# microSD_Display.net
KiCad netlist of a schematic drawn in Altium Designer
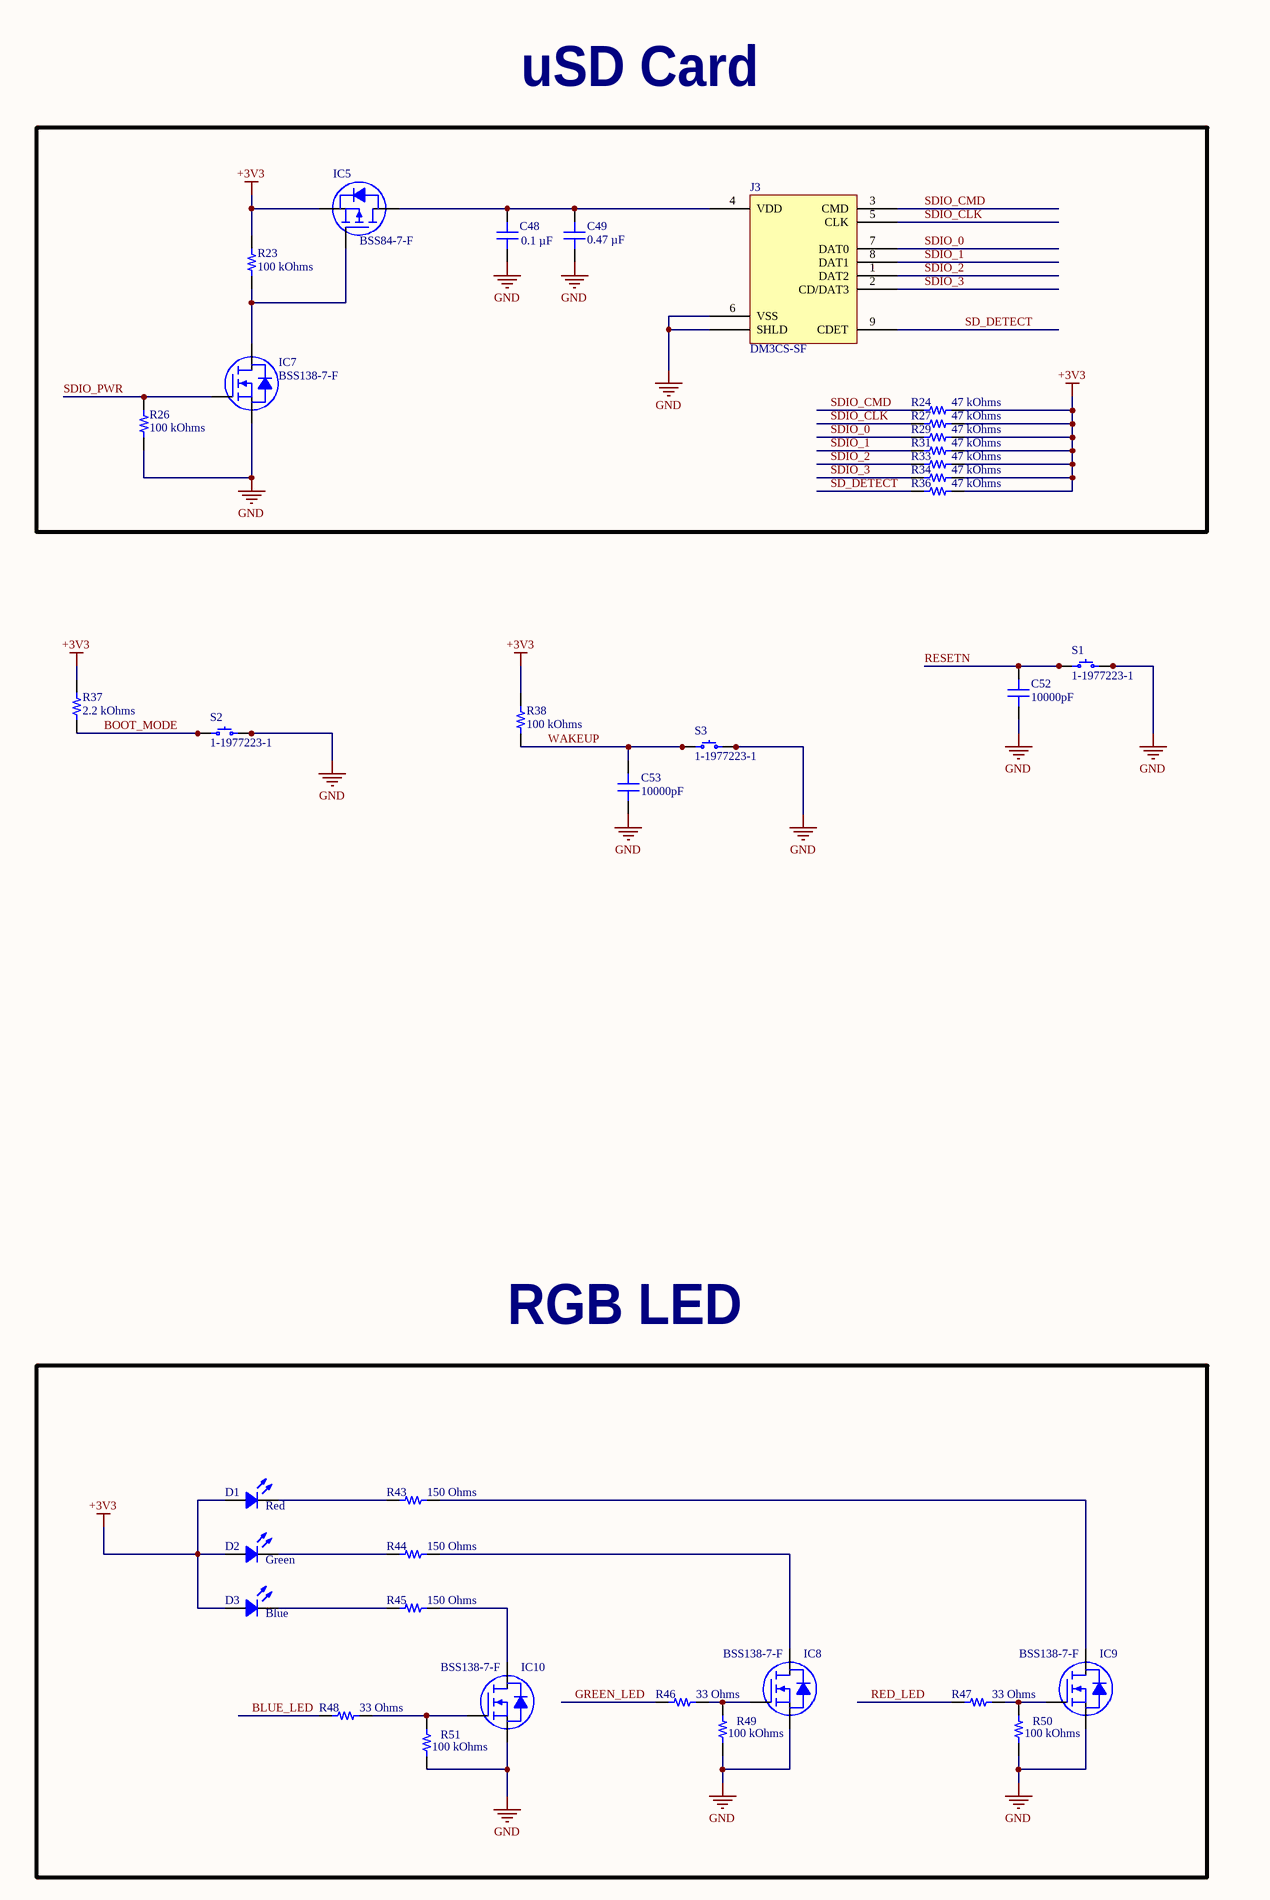
[diagram p0: microSD_Display.SchDoc, left]
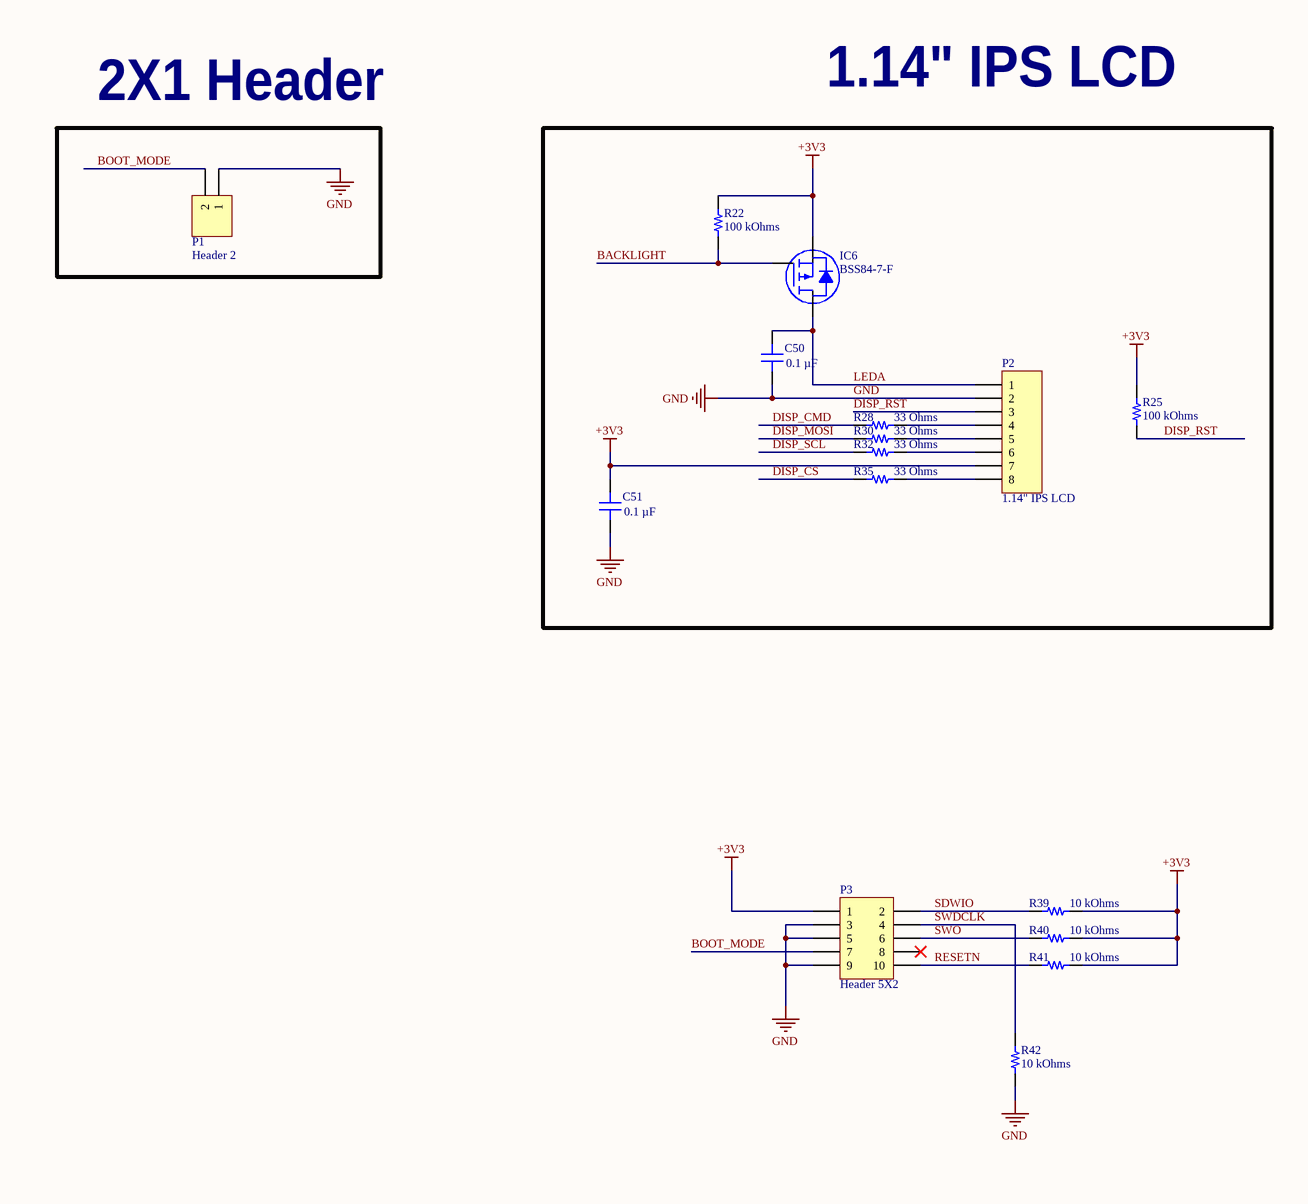
[diagram p1: microSD_Display.SchDoc, right]

(export (version "E")
  (design (tool "Eeschema 10.0.6"))
  (components
    (comp (ref "C48")
      (value "0.1 µF")
      (footprint "CAP 0603_1608")
      (description "CAP CER 0.1UF 16V X7R 0603")
      (fields (field (name "PART NUMBER") "CS0603KRX7R7BB104") (field (name "MANUFACTURER") "Yageo"))
      (libsource (lib "Celestial Altium Library - altium_library") (part "Capacitor"))
    )
    (comp (ref "C49")
      (value "0.47 µF")
      (footprint "CAP 0603_1608")
      (description "CAP CER 0.47UF 16V X5R 0603")
      (fields
        (field (name "PART NUMBER") "0603X474K160CT")
        (field (name "MANUFACTURER") "Walsin Technology Corporation")
      )
      (libsource (lib "Celestial Altium Library - altium_library") (part "Capacitor"))
    )
    (comp (ref "C50")
      (value "0.1 µF")
      (footprint "CAP 0603_1608")
      (description "CAP CER 0.1UF 16V X7R 0603")
      (fields (field (name "PART NUMBER") "CS0603KRX7R7BB104") (field (name "MANUFACTURER") "Yageo"))
      (libsource (lib "Celestial Altium Library - altium_library") (part "Capacitor"))
    )
    (comp (ref "C51")
      (value "0.1 µF")
      (footprint "CAP 0603_1608")
      (description "CAP CER 0.1UF 16V X7R 0603")
      (fields (field (name "PART NUMBER") "CS0603KRX7R7BB104") (field (name "MANUFACTURER") "Yageo"))
      (libsource (lib "Celestial Altium Library - altium_library") (part "Capacitor"))
    )
    (comp (ref "C52")
      (value "10000pF")
      (footprint "CAP 0603_1608")
      (description "CAP CER 10000PF 16V X7R 0603")
      (fields (field (name "PART NUMBER") "0603YC103KAT2A") (field (name "MANUFACTURER") "AVX Corporation"))
      (libsource (lib "Celestial Altium Library - altium_library") (part "Capacitor"))
    )
    (comp (ref "C53")
      (value "10000pF")
      (footprint "CAP 0603_1608")
      (description "CAP CER 10000PF 16V X7R 0603")
      (fields (field (name "PART NUMBER") "0603YC103KAT2A") (field (name "MANUFACTURER") "AVX Corporation"))
      (libsource (lib "Celestial Altium Library - altium_library") (part "Capacitor"))
    )
    (comp (ref "D1")
      (value "Red")
      (footprint "LED 0603_1608 RED")
      (description "LED RED DIFFUSED SURFACE MOUNT")
      (fields (field (name "PART NUMBER") "FKR1111C-TR") (field (name "MANUFACTURER") "Stanley Electric Co"))
      (libsource (lib "Celestial Altium Library - altium_library") (part "LED"))
    )
    (comp (ref "D2")
      (value "Green")
      (footprint "LED 0603_1608 GREEN")
      (description "LED GREEN DIFFUSED 0603 SMD")
      (fields (field (name "PART NUMBER") "HSME-C130") (field (name "MANUFACTURER") "Broadcom Limited"))
      (libsource (lib "Celestial Altium Library - altium_library") (part "LED"))
    )
    (comp (ref "D3")
      (value "Blue")
      (footprint "LED 0603_1608 BLUE")
      (description "LED BLUE 0603 SMD")
      (fields (field (name "PART NUMBER") "5973604507F") (field (name "MANUFACTURER") "Dialight"))
      (libsource (lib "Celestial Altium Library - altium_library") (part "LED"))
    )
    (comp (ref "IC5")
      (value "BSS84-7-F")
      (footprint "DIODES SOT-23-3")
      (description "MOSFET P-CH 50V 130MA SOT23-3")
      (fields (field (name "MANUFACTURER") "Diodes Incorporated"))
      (libsource (lib "Celestial Altium Library - altium_library") (part "DIODES MOSFET P-CH SOT-23-3"))
    )
    (comp (ref "IC6")
      (value "BSS84-7-F")
      (footprint "DIODES SOT-23-3")
      (description "MOSFET P-CH 50V 130MA SOT23-3")
      (fields (field (name "MANUFACTURER") "Diodes Incorporated"))
      (libsource (lib "Celestial Altium Library - altium_library") (part "DIODES MOSFET P-CH SOT-23-3"))
    )
    (comp (ref "IC7")
      (value "BSS138-7-F")
      (footprint "DIODES SOT-23-3")
      (description "MOSFET N-CH 50V 200MA SOT23-3")
      (fields (field (name "MANUFACTURER") "Diodes Incorporated"))
      (libsource (lib "Celestial Altium Library - altium_library") (part "DIODES INC MOSFET N-CH SOT-23-3"))
    )
    (comp (ref "IC8")
      (value "BSS138-7-F")
      (footprint "DIODES SOT-23-3")
      (description "MOSFET N-CH 50V 200MA SOT23-3")
      (fields (field (name "MANUFACTURER") "Diodes Incorporated"))
      (libsource (lib "Celestial Altium Library - altium_library") (part "DIODES INC MOSFET N-CH SOT-23-3"))
    )
    (comp (ref "IC9")
      (value "BSS138-7-F")
      (footprint "DIODES SOT-23-3")
      (description "MOSFET N-CH 50V 200MA SOT23-3")
      (fields (field (name "MANUFACTURER") "Diodes Incorporated"))
      (libsource (lib "Celestial Altium Library - altium_library") (part "DIODES INC MOSFET N-CH SOT-23-3"))
    )
    (comp (ref "IC10")
      (value "BSS138-7-F")
      (footprint "DIODES SOT-23-3")
      (description "MOSFET N-CH 50V 200MA SOT23-3")
      (fields (field (name "MANUFACTURER") "Diodes Incorporated"))
      (libsource (lib "Celestial Altium Library - altium_library") (part "DIODES INC MOSFET N-CH SOT-23-3"))
    )
    (comp (ref "J3")
      (value "DM3CS-SF")
      (footprint "HIROSE DM3CS")
      (description "CONN MICRO SD CARD HINGED TYPE")
      (fields (field (name "MANUFACTURER") "Hirose Electric Co Ltd"))
      (libsource (lib "Celestial Altium Library - altium_library") (part "Hirose DM3C MicroSD"))
    )
    (comp (ref "P1")
      (value "Header 2")
      (footprint "HDR1X2")
      (description "Header, 2-Pin")
      (fields (field (name "PUBLISHER") "Altium Limited"))
      (libsource (lib "Miscellaneous Connectors") (part "Header 2"))
    )
    (comp (ref "P2")
      (value "1.14\" IPS LCD")
      (footprint "HDR1X8")
      (description "Header, 8-Pin")
      (fields (field (name "PUBLISHER") "Altium Limited"))
      (libsource (lib "Miscellaneous Connectors") (part "Header 8"))
    )
    (comp (ref "P3")
      (value "Header 5X2")
      (footprint "HDR2X5")
      (description "Header, 5-Pin, Dual row")
      (fields (field (name "PUBLISHER") "Altium Limited"))
      (libsource (lib "Miscellaneous Connectors") (part "Header 5X2"))
    )
    (comp (ref "R22")
      (value "100 kOhms")
      (footprint "RES 0603_1608")
      (description "RES 100 KOHMS 0.5% 1/10W 0603")
      (fields
        (field (name "PART NUMBER") "ERA-3AED104V")
        (field (name "MANUFACTURER") "Panasonic Electronic Components")
      )
      (libsource (lib "Celestial Altium Library - altium_library") (part "Resistor"))
    )
    (comp (ref "R23")
      (value "100 kOhms")
      (footprint "RES 0603_1608")
      (description "RES 100 KOHMS 0.5% 1/10W 0603")
      (fields
        (field (name "PART NUMBER") "ERA-3AED104V")
        (field (name "MANUFACTURER") "Panasonic Electronic Components")
      )
      (libsource (lib "Celestial Altium Library - altium_library") (part "Resistor"))
    )
    (comp (ref "R24")
      (value "47 kOhms")
      (footprint "RES 0603_1608")
      (description "RES 47K OHM 5% 1/4W 0603")
      (fields
        (field (name "PART NUMBER") "ERJ-UP3J473V")
        (field (name "MANUFACTURER") "Panasonic Electronic Components")
      )
      (libsource (lib "Celestial Altium Library - altium_library") (part "Resistor"))
    )
    (comp (ref "R25")
      (value "100 kOhms")
      (footprint "RES 0603_1608")
      (description "RES 100 KOHMS 0.5% 1/10W 0603")
      (fields
        (field (name "PART NUMBER") "ERA-3AED104V")
        (field (name "MANUFACTURER") "Panasonic Electronic Components")
      )
      (libsource (lib "Celestial Altium Library - altium_library") (part "Resistor"))
    )
    (comp (ref "R26")
      (value "100 kOhms")
      (footprint "RES 0603_1608")
      (description "RES 100 KOHMS 0.5% 1/10W 0603")
      (fields
        (field (name "PART NUMBER") "ERA-3AED104V")
        (field (name "MANUFACTURER") "Panasonic Electronic Components")
      )
      (libsource (lib "Celestial Altium Library - altium_library") (part "Resistor"))
    )
    (comp (ref "R27")
      (value "47 kOhms")
      (footprint "RES 0603_1608")
      (description "RES 47K OHM 5% 1/4W 0603")
      (fields
        (field (name "PART NUMBER") "ERJ-UP3J473V")
        (field (name "MANUFACTURER") "Panasonic Electronic Components")
      )
      (libsource (lib "Celestial Altium Library - altium_library") (part "Resistor"))
    )
    (comp (ref "R28")
      (value "33 Ohms")
      (footprint "RES 0603_1608")
      (description "RES SMD 33 OHM 1% 1/10W 0603")
      (fields (field (name "PART NUMBER") "AC0603FR-0733RL") (field (name "MANUFACTURER") "Yageo"))
      (libsource (lib "Celestial Altium Library - altium_library") (part "Resistor"))
    )
    (comp (ref "R29")
      (value "47 kOhms")
      (footprint "RES 0603_1608")
      (description "RES 47K OHM 5% 1/4W 0603")
      (fields
        (field (name "PART NUMBER") "ERJ-UP3J473V")
        (field (name "MANUFACTURER") "Panasonic Electronic Components")
      )
      (libsource (lib "Celestial Altium Library - altium_library") (part "Resistor"))
    )
    (comp (ref "R30")
      (value "33 Ohms")
      (footprint "RES 0603_1608")
      (description "RES SMD 33 OHM 1% 1/10W 0603")
      (fields (field (name "PART NUMBER") "AC0603FR-0733RL") (field (name "MANUFACTURER") "Yageo"))
      (libsource (lib "Celestial Altium Library - altium_library") (part "Resistor"))
    )
    (comp (ref "R31")
      (value "47 kOhms")
      (footprint "RES 0603_1608")
      (description "RES 47K OHM 5% 1/4W 0603")
      (fields
        (field (name "PART NUMBER") "ERJ-UP3J473V")
        (field (name "MANUFACTURER") "Panasonic Electronic Components")
      )
      (libsource (lib "Celestial Altium Library - altium_library") (part "Resistor"))
    )
    (comp (ref "R32")
      (value "33 Ohms")
      (footprint "RES 0603_1608")
      (description "RES SMD 33 OHM 1% 1/10W 0603")
      (fields (field (name "PART NUMBER") "AC0603FR-0733RL") (field (name "MANUFACTURER") "Yageo"))
      (libsource (lib "Celestial Altium Library - altium_library") (part "Resistor"))
    )
    (comp (ref "R33")
      (value "47 kOhms")
      (footprint "RES 0603_1608")
      (description "RES 47K OHM 5% 1/4W 0603")
      (fields
        (field (name "PART NUMBER") "ERJ-UP3J473V")
        (field (name "MANUFACTURER") "Panasonic Electronic Components")
      )
      (libsource (lib "Celestial Altium Library - altium_library") (part "Resistor"))
    )
    (comp (ref "R34")
      (value "47 kOhms")
      (footprint "RES 0603_1608")
      (description "RES 47K OHM 5% 1/4W 0603")
      (fields
        (field (name "PART NUMBER") "ERJ-UP3J473V")
        (field (name "MANUFACTURER") "Panasonic Electronic Components")
      )
      (libsource (lib "Celestial Altium Library - altium_library") (part "Resistor"))
    )
    (comp (ref "R35")
      (value "33 Ohms")
      (footprint "RES 0603_1608")
      (description "RES SMD 33 OHM 1% 1/10W 0603")
      (fields (field (name "PART NUMBER") "AC0603FR-0733RL") (field (name "MANUFACTURER") "Yageo"))
      (libsource (lib "Celestial Altium Library - altium_library") (part "Resistor"))
    )
    (comp (ref "R36")
      (value "47 kOhms")
      (footprint "RES 0603_1608")
      (description "RES 47K OHM 5% 1/4W 0603")
      (fields
        (field (name "PART NUMBER") "ERJ-UP3J473V")
        (field (name "MANUFACTURER") "Panasonic Electronic Components")
      )
      (libsource (lib "Celestial Altium Library - altium_library") (part "Resistor"))
    )
    (comp (ref "R37")
      (value "2.2 kOhms")
      (footprint "RES 0603_1608")
      (description "RES SMD 2.2K OHM 1% 1/10W 0603")
      (fields (field (name "PART NUMBER") "AC0603FR-072K2L") (field (name "MANUFACTURER") "Yageo"))
      (libsource (lib "Celestial Altium Library - altium_library") (part "Resistor"))
    )
    (comp (ref "R38")
      (value "100 kOhms")
      (footprint "RES 0603_1608")
      (description "RES 100 KOHMS 0.5% 1/10W 0603")
      (fields
        (field (name "PART NUMBER") "ERA-3AED104V")
        (field (name "MANUFACTURER") "Panasonic Electronic Components")
      )
      (libsource (lib "Celestial Altium Library - altium_library") (part "Resistor"))
    )
    (comp (ref "R39")
      (value "10 kOhms")
      (footprint "RES 0603_1608")
      (description "RES SMD 10K OHM 1% 1/10W 0603")
      (fields (field (name "PART NUMBER") "AA0603FR-0710KL") (field (name "MANUFACTURER") "Yageo"))
      (libsource (lib "Celestial Altium Library - altium_library") (part "Resistor"))
    )
    (comp (ref "R40")
      (value "10 kOhms")
      (footprint "RES 0603_1608")
      (description "RES SMD 10K OHM 1% 1/10W 0603")
      (fields (field (name "PART NUMBER") "AA0603FR-0710KL") (field (name "MANUFACTURER") "Yageo"))
      (libsource (lib "Celestial Altium Library - altium_library") (part "Resistor"))
    )
    (comp (ref "R41")
      (value "10 kOhms")
      (footprint "RES 0603_1608")
      (description "RES SMD 10K OHM 1% 1/10W 0603")
      (fields (field (name "PART NUMBER") "AA0603FR-0710KL") (field (name "MANUFACTURER") "Yageo"))
      (libsource (lib "Celestial Altium Library - altium_library") (part "Resistor"))
    )
    (comp (ref "R42")
      (value "10 kOhms")
      (footprint "RES 0603_1608")
      (description "RES SMD 10K OHM 1% 1/10W 0603")
      (fields (field (name "PART NUMBER") "AA0603FR-0710KL") (field (name "MANUFACTURER") "Yageo"))
      (libsource (lib "Celestial Altium Library - altium_library") (part "Resistor"))
    )
    (comp (ref "R43")
      (value "150 Ohms")
      (footprint "RES 0603_1608")
      (description "RES SMD 150 OHM 5% 1/10W 0603")
      (fields (field (name "PART NUMBER") "CR0603-JW-151ELF") (field (name "MANUFACTURER") "Bourns Inc."))
      (libsource (lib "Celestial Altium Library - altium_library") (part "Resistor"))
    )
    (comp (ref "R44")
      (value "150 Ohms")
      (footprint "RES 0603_1608")
      (description "RES SMD 150 OHM 5% 1/10W 0603")
      (fields (field (name "PART NUMBER") "CR0603-JW-151ELF") (field (name "MANUFACTURER") "Bourns Inc."))
      (libsource (lib "Celestial Altium Library - altium_library") (part "Resistor"))
    )
    (comp (ref "R45")
      (value "150 Ohms")
      (footprint "RES 0603_1608")
      (description "RES SMD 150 OHM 5% 1/10W 0603")
      (fields (field (name "PART NUMBER") "CR0603-JW-151ELF") (field (name "MANUFACTURER") "Bourns Inc."))
      (libsource (lib "Celestial Altium Library - altium_library") (part "Resistor"))
    )
    (comp (ref "R46")
      (value "33 Ohms")
      (footprint "RES 0603_1608")
      (description "RES SMD 33 OHM 1% 1/10W 0603")
      (fields (field (name "PART NUMBER") "AC0603FR-0733RL") (field (name "MANUFACTURER") "Yageo"))
      (libsource (lib "Celestial Altium Library - altium_library") (part "Resistor"))
    )
    (comp (ref "R47")
      (value "33 Ohms")
      (footprint "RES 0603_1608")
      (description "RES SMD 33 OHM 1% 1/10W 0603")
      (fields (field (name "PART NUMBER") "AC0603FR-0733RL") (field (name "MANUFACTURER") "Yageo"))
      (libsource (lib "Celestial Altium Library - altium_library") (part "Resistor"))
    )
    (comp (ref "R48")
      (value "33 Ohms")
      (footprint "RES 0603_1608")
      (description "RES SMD 33 OHM 1% 1/10W 0603")
      (fields (field (name "PART NUMBER") "AC0603FR-0733RL") (field (name "MANUFACTURER") "Yageo"))
      (libsource (lib "Celestial Altium Library - altium_library") (part "Resistor"))
    )
    (comp (ref "R49")
      (value "100 kOhms")
      (footprint "RES 0603_1608")
      (description "RES 100 KOHMS 0.5% 1/10W 0603")
      (fields
        (field (name "PART NUMBER") "ERA-3AED104V")
        (field (name "MANUFACTURER") "Panasonic Electronic Components")
      )
      (libsource (lib "Celestial Altium Library - altium_library") (part "Resistor"))
    )
    (comp (ref "R50")
      (value "100 kOhms")
      (footprint "RES 0603_1608")
      (description "RES 100 KOHMS 0.5% 1/10W 0603")
      (fields
        (field (name "PART NUMBER") "ERA-3AED104V")
        (field (name "MANUFACTURER") "Panasonic Electronic Components")
      )
      (libsource (lib "Celestial Altium Library - altium_library") (part "Resistor"))
    )
    (comp (ref "R51")
      (value "100 kOhms")
      (footprint "RES 0603_1608")
      (description "RES 100 KOHMS 0.5% 1/10W 0603")
      (fields
        (field (name "PART NUMBER") "ERA-3AED104V")
        (field (name "MANUFACTURER") "Panasonic Electronic Components")
      )
      (libsource (lib "Celestial Altium Library - altium_library") (part "Resistor"))
    )
    (comp (ref "S1")
      (value "1-1977223-1")
      (footprint "TE FSM4JSMA")
      (description "SWITCH TACTILE SPST-NO 0.05A 24V")
      (fields (field (name "MANUFACTURER") "TE Connectivity ALCOSWITCH Switches"))
      (libsource (lib "Celestial Altium Library - altium_library") (part "SPST-NO 4 PIN"))
    )
    (comp (ref "S2")
      (value "1-1977223-1")
      (footprint "TE FSM4JSMA")
      (description "SWITCH TACTILE SPST-NO 0.05A 24V")
      (fields (field (name "MANUFACTURER") "TE Connectivity ALCOSWITCH Switches"))
      (libsource (lib "Celestial Altium Library - altium_library") (part "SPST-NO 4 PIN"))
    )
    (comp (ref "S3")
      (value "1-1977223-1")
      (footprint "TE FSM4JSMA")
      (description "SWITCH TACTILE SPST-NO 0.05A 24V")
      (fields (field (name "MANUFACTURER") "TE Connectivity ALCOSWITCH Switches"))
      (libsource (lib "Celestial Altium Library - altium_library") (part "SPST-NO 4 PIN"))
    )
  )
  (nets
    (net (code "1") (name "+3V3") (class "Default")
      (node (ref "C51") (pin "2") (pinfunction "2_2") (pintype "passive"))
      (node (ref "D1") (pin "1") (pinfunction "1_1") (pintype "passive"))
      (node (ref "D2") (pin "1") (pinfunction "1_1") (pintype "passive"))
      (node (ref "D3") (pin "1") (pinfunction "1_1") (pintype "passive"))
      (node (ref "IC5") (pin "2") (pinfunction "S_2") (pintype "passive"))
      (node (ref "IC6") (pin "2") (pinfunction "S_2") (pintype "passive"))
      (node (ref "P2") (pin "7") (pinfunction "7_7") (pintype "passive"))
      (node (ref "P3") (pin "1") (pinfunction "1_1") (pintype "passive"))
      (node (ref "R22") (pin "2") (pinfunction "2_2") (pintype "passive"))
      (node (ref "R23") (pin "2") (pinfunction "2_2") (pintype "passive"))
      (node (ref "R24") (pin "2") (pinfunction "2_2") (pintype "passive"))
      (node (ref "R25") (pin "2") (pinfunction "2_2") (pintype "passive"))
      (node (ref "R27") (pin "2") (pinfunction "2_2") (pintype "passive"))
      (node (ref "R29") (pin "2") (pinfunction "2_2") (pintype "passive"))
      (node (ref "R31") (pin "2") (pinfunction "2_2") (pintype "passive"))
      (node (ref "R33") (pin "2") (pinfunction "2_2") (pintype "passive"))
      (node (ref "R34") (pin "2") (pinfunction "2_2") (pintype "passive"))
      (node (ref "R36") (pin "2") (pinfunction "2_2") (pintype "passive"))
      (node (ref "R37") (pin "2") (pinfunction "2_2") (pintype "passive"))
      (node (ref "R38") (pin "2") (pinfunction "2_2") (pintype "passive"))
      (node (ref "R39") (pin "2") (pinfunction "2_2") (pintype "passive"))
      (node (ref "R40") (pin "2") (pinfunction "2_2") (pintype "passive"))
      (node (ref "R41") (pin "2") (pinfunction "2_2") (pintype "passive"))
    )
    (net (code "2") (name "/BACKLIGHT") (class "Default")
      (node (ref "IC6") (pin "1") (pinfunction "G_1") (pintype "passive"))
      (node (ref "R22") (pin "1") (pinfunction "1_1") (pintype "passive"))
    )
    (net (code "3") (name "/BLUE_LED") (class "Default")
      (node (ref "R48") (pin "1") (pinfunction "1_1") (pintype "passive"))
    )
    (net (code "4") (name "/BOOT_MODE") (class "Default")
      (node (ref "P1") (pin "2") (pinfunction "2_2") (pintype "passive"))
      (node (ref "P3") (pin "7") (pinfunction "7_7") (pintype "passive"))
      (node (ref "R37") (pin "1") (pinfunction "1_1") (pintype "passive"))
      (node (ref "S2") (pin "1") (pinfunction "1_1") (pintype "passive"))
      (node (ref "S2") (pin "2") (pinfunction "2_2") (pintype "passive"))
    )
    (net (code "5") (name "/DISP_CMD") (class "Default")
      (node (ref "R28") (pin "1") (pinfunction "1_1") (pintype "passive"))
    )
    (net (code "6") (name "/DISP_CS") (class "Default")
      (node (ref "R35") (pin "1") (pinfunction "1_1") (pintype "passive"))
    )
    (net (code "7") (name "/DISP_MOSI") (class "Default")
      (node (ref "R30") (pin "1") (pinfunction "1_1") (pintype "passive"))
    )
    (net (code "8") (name "/DISP_RST") (class "Default")
      (node (ref "P2") (pin "3") (pinfunction "3_3") (pintype "passive"))
      (node (ref "R25") (pin "1") (pinfunction "1_1") (pintype "passive"))
    )
    (net (code "9") (name "/DISP_SCL") (class "Default")
      (node (ref "R32") (pin "1") (pinfunction "1_1") (pintype "passive"))
    )
    (net (code "10") (name "/GREEN_LED") (class "Default")
      (node (ref "R46") (pin "1") (pinfunction "1_1") (pintype "passive"))
    )
    (net (code "11") (name "/LEDA") (class "Default")
      (node (ref "C50") (pin "2") (pinfunction "2_2") (pintype "passive"))
      (node (ref "IC6") (pin "3") (pinfunction "D_3") (pintype "passive"))
      (node (ref "P2") (pin "1") (pinfunction "1_1") (pintype "passive"))
    )
    (net (code "12") (name "/RED_LED") (class "Default")
      (node (ref "R47") (pin "1") (pinfunction "1_1") (pintype "passive"))
    )
    (net (code "13") (name "/RESETN") (class "Default")
      (node (ref "C52") (pin "2") (pinfunction "2_2") (pintype "passive"))
      (node (ref "P3") (pin "10") (pinfunction "10_10") (pintype "passive"))
      (node (ref "R41") (pin "1") (pinfunction "1_1") (pintype "passive"))
      (node (ref "S1") (pin "1") (pinfunction "1_1") (pintype "passive"))
      (node (ref "S1") (pin "2") (pinfunction "2_2") (pintype "passive"))
    )
    (net (code "14") (name "/SDIO_0") (class "Default")
      (node (ref "J3") (pin "7") (pinfunction "DAT0_7") (pintype "passive"))
      (node (ref "R29") (pin "1") (pinfunction "1_1") (pintype "passive"))
    )
    (net (code "15") (name "/SDIO_1") (class "Default")
      (node (ref "J3") (pin "8") (pinfunction "DAT1_8") (pintype "passive"))
      (node (ref "R31") (pin "1") (pinfunction "1_1") (pintype "passive"))
    )
    (net (code "16") (name "/SDIO_2") (class "Default")
      (node (ref "J3") (pin "1") (pinfunction "DAT2_1") (pintype "passive"))
      (node (ref "R33") (pin "1") (pinfunction "1_1") (pintype "passive"))
    )
    (net (code "17") (name "/SDIO_3") (class "Default")
      (node (ref "J3") (pin "2") (pinfunction "CD/DAT3_2") (pintype "passive"))
      (node (ref "R34") (pin "1") (pinfunction "1_1") (pintype "passive"))
    )
    (net (code "18") (name "/SDIO_CLK") (class "Default")
      (node (ref "J3") (pin "5") (pinfunction "CLK_5") (pintype "passive"))
      (node (ref "R27") (pin "1") (pinfunction "1_1") (pintype "passive"))
    )
    (net (code "19") (name "/SDIO_CMD") (class "Default")
      (node (ref "J3") (pin "3") (pinfunction "CMD_3") (pintype "passive"))
      (node (ref "R24") (pin "1") (pinfunction "1_1") (pintype "passive"))
    )
    (net (code "20") (name "/SDIO_PWR") (class "Default")
      (node (ref "IC7") (pin "1") (pinfunction "G_1") (pintype "passive"))
      (node (ref "R26") (pin "2") (pinfunction "2_2") (pintype "passive"))
    )
    (net (code "21") (name "/SDWIO") (class "Default")
      (node (ref "P3") (pin "2") (pinfunction "2_2") (pintype "passive"))
      (node (ref "R39") (pin "1") (pinfunction "1_1") (pintype "passive"))
    )
    (net (code "22") (name "/SD_DETECT") (class "Default")
      (node (ref "J3") (pin "9") (pinfunction "CDET_9") (pintype "passive"))
      (node (ref "R36") (pin "1") (pinfunction "1_1") (pintype "passive"))
    )
    (net (code "23") (name "/SWDCLK") (class "Default")
      (node (ref "P3") (pin "4") (pinfunction "4_4") (pintype "passive"))
      (node (ref "R42") (pin "2") (pinfunction "2_2") (pintype "passive"))
    )
    (net (code "24") (name "/SWO") (class "Default")
      (node (ref "P3") (pin "6") (pinfunction "6_6") (pintype "passive"))
      (node (ref "R40") (pin "1") (pinfunction "1_1") (pintype "passive"))
    )
    (net (code "25") (name "/WAKEUP") (class "Default")
      (node (ref "C53") (pin "2") (pinfunction "2_2") (pintype "passive"))
      (node (ref "R38") (pin "1") (pinfunction "1_1") (pintype "passive"))
      (node (ref "S3") (pin "1") (pinfunction "1_1") (pintype "passive"))
      (node (ref "S3") (pin "2") (pinfunction "2_2") (pintype "passive"))
    )
    (net (code "26") (name "GND") (class "Default")
      (node (ref "C48") (pin "1") (pinfunction "1_1") (pintype "passive"))
      (node (ref "C49") (pin "1") (pinfunction "1_1") (pintype "passive"))
      (node (ref "C50") (pin "1") (pinfunction "1_1") (pintype "passive"))
      (node (ref "C51") (pin "1") (pinfunction "1_1") (pintype "passive"))
      (node (ref "C52") (pin "1") (pinfunction "1_1") (pintype "passive"))
      (node (ref "C53") (pin "1") (pinfunction "1_1") (pintype "passive"))
      (node (ref "IC10") (pin "2") (pinfunction "S_2") (pintype "passive"))
      (node (ref "IC7") (pin "2") (pinfunction "S_2") (pintype "passive"))
      (node (ref "IC8") (pin "2") (pinfunction "S_2") (pintype "passive"))
      (node (ref "IC9") (pin "2") (pinfunction "S_2") (pintype "passive"))
      (node (ref "J3") (pin "6") (pinfunction "VSS_6") (pintype "passive"))
      (node (ref "J3") (pin "S") (pinfunction "SHLD_S") (pintype "passive"))
      (node (ref "P1") (pin "1") (pinfunction "1_1") (pintype "passive"))
      (node (ref "P2") (pin "2") (pinfunction "2_2") (pintype "passive"))
      (node (ref "P3") (pin "3") (pinfunction "3_3") (pintype "passive"))
      (node (ref "P3") (pin "5") (pinfunction "5_5") (pintype "passive"))
      (node (ref "P3") (pin "9") (pinfunction "9_9") (pintype "passive"))
      (node (ref "R26") (pin "1") (pinfunction "1_1") (pintype "passive"))
      (node (ref "R42") (pin "1") (pinfunction "1_1") (pintype "passive"))
      (node (ref "R49") (pin "1") (pinfunction "1_1") (pintype "passive"))
      (node (ref "R50") (pin "1") (pinfunction "1_1") (pintype "passive"))
      (node (ref "R51") (pin "1") (pinfunction "1_1") (pintype "passive"))
      (node (ref "S1") (pin "3") (pinfunction "3_3") (pintype "passive"))
      (node (ref "S1") (pin "4") (pinfunction "4_4") (pintype "passive"))
      (node (ref "S2") (pin "3") (pinfunction "3_3") (pintype "passive"))
      (node (ref "S2") (pin "4") (pinfunction "4_4") (pintype "passive"))
      (node (ref "S3") (pin "3") (pinfunction "3_3") (pintype "passive"))
      (node (ref "S3") (pin "4") (pinfunction "4_4") (pintype "passive"))
    )
    (net (code "27") (name "Net-(D1-Pad2)") (class "Default")
      (node (ref "D1") (pin "2") (pinfunction "2_2") (pintype "passive"))
      (node (ref "R43") (pin "1") (pinfunction "1_1") (pintype "passive"))
    )
    (net (code "28") (name "Net-(D2-Pad2)") (class "Default")
      (node (ref "D2") (pin "2") (pinfunction "2_2") (pintype "passive"))
      (node (ref "R44") (pin "1") (pinfunction "1_1") (pintype "passive"))
    )
    (net (code "29") (name "Net-(D3-Pad2)") (class "Default")
      (node (ref "D3") (pin "2") (pinfunction "2_2") (pintype "passive"))
      (node (ref "R45") (pin "1") (pinfunction "1_1") (pintype "passive"))
    )
    (net (code "30") (name "Net-(IC5-D)") (class "Default")
      (node (ref "C48") (pin "2") (pinfunction "2_2") (pintype "passive"))
      (node (ref "C49") (pin "2") (pinfunction "2_2") (pintype "passive"))
      (node (ref "IC5") (pin "3") (pinfunction "D_3") (pintype "passive"))
      (node (ref "J3") (pin "4") (pinfunction "VDD_4") (pintype "passive"))
    )
    (net (code "31") (name "Net-(IC5-G)") (class "Default")
      (node (ref "IC5") (pin "1") (pinfunction "G_1") (pintype "passive"))
      (node (ref "IC7") (pin "3") (pinfunction "D_3") (pintype "passive"))
      (node (ref "R23") (pin "1") (pinfunction "1_1") (pintype "passive"))
    )
    (net (code "32") (name "Net-(IC8-D)") (class "Default")
      (node (ref "IC8") (pin "3") (pinfunction "D_3") (pintype "passive"))
      (node (ref "R44") (pin "2") (pinfunction "2_2") (pintype "passive"))
    )
    (net (code "33") (name "Net-(IC8-G)") (class "Default")
      (node (ref "IC8") (pin "1") (pinfunction "G_1") (pintype "passive"))
      (node (ref "R46") (pin "2") (pinfunction "2_2") (pintype "passive"))
      (node (ref "R49") (pin "2") (pinfunction "2_2") (pintype "passive"))
    )
    (net (code "34") (name "Net-(IC9-D)") (class "Default")
      (node (ref "IC9") (pin "3") (pinfunction "D_3") (pintype "passive"))
      (node (ref "R43") (pin "2") (pinfunction "2_2") (pintype "passive"))
    )
    (net (code "35") (name "Net-(IC9-G)") (class "Default")
      (node (ref "IC9") (pin "1") (pinfunction "G_1") (pintype "passive"))
      (node (ref "R47") (pin "2") (pinfunction "2_2") (pintype "passive"))
      (node (ref "R50") (pin "2") (pinfunction "2_2") (pintype "passive"))
    )
    (net (code "36") (name "Net-(IC10-D)") (class "Default")
      (node (ref "IC10") (pin "3") (pinfunction "D_3") (pintype "passive"))
      (node (ref "R45") (pin "2") (pinfunction "2_2") (pintype "passive"))
    )
    (net (code "37") (name "Net-(IC10-G)") (class "Default")
      (node (ref "IC10") (pin "1") (pinfunction "G_1") (pintype "passive"))
      (node (ref "R48") (pin "2") (pinfunction "2_2") (pintype "passive"))
      (node (ref "R51") (pin "2") (pinfunction "2_2") (pintype "passive"))
    )
    (net (code "38") (name "Net-(P2-Pad4)") (class "Default")
      (node (ref "P2") (pin "4") (pinfunction "4_4") (pintype "passive"))
      (node (ref "R28") (pin "2") (pinfunction "2_2") (pintype "passive"))
    )
    (net (code "39") (name "Net-(P2-Pad5)") (class "Default")
      (node (ref "P2") (pin "5") (pinfunction "5_5") (pintype "passive"))
      (node (ref "R30") (pin "2") (pinfunction "2_2") (pintype "passive"))
    )
    (net (code "40") (name "Net-(P2-Pad6)") (class "Default")
      (node (ref "P2") (pin "6") (pinfunction "6_6") (pintype "passive"))
      (node (ref "R32") (pin "2") (pinfunction "2_2") (pintype "passive"))
    )
    (net (code "41") (name "Net-(P2-Pad8)") (class "Default")
      (node (ref "P2") (pin "8") (pinfunction "8_8") (pintype "passive"))
      (node (ref "R35") (pin "2") (pinfunction "2_2") (pintype "passive"))
    )
    (net (code "42") (name "unconnected-(P3-Pad8)") (class "Default")
      (node (ref "P3") (pin "8") (pinfunction "8_8") (pintype "passive+no_connect"))
    )
  )
)
